# SAMV71_Xplained_Ultra_Shield_Connectors.net
KiCad netlist of a schematic drawn in Altium Designer
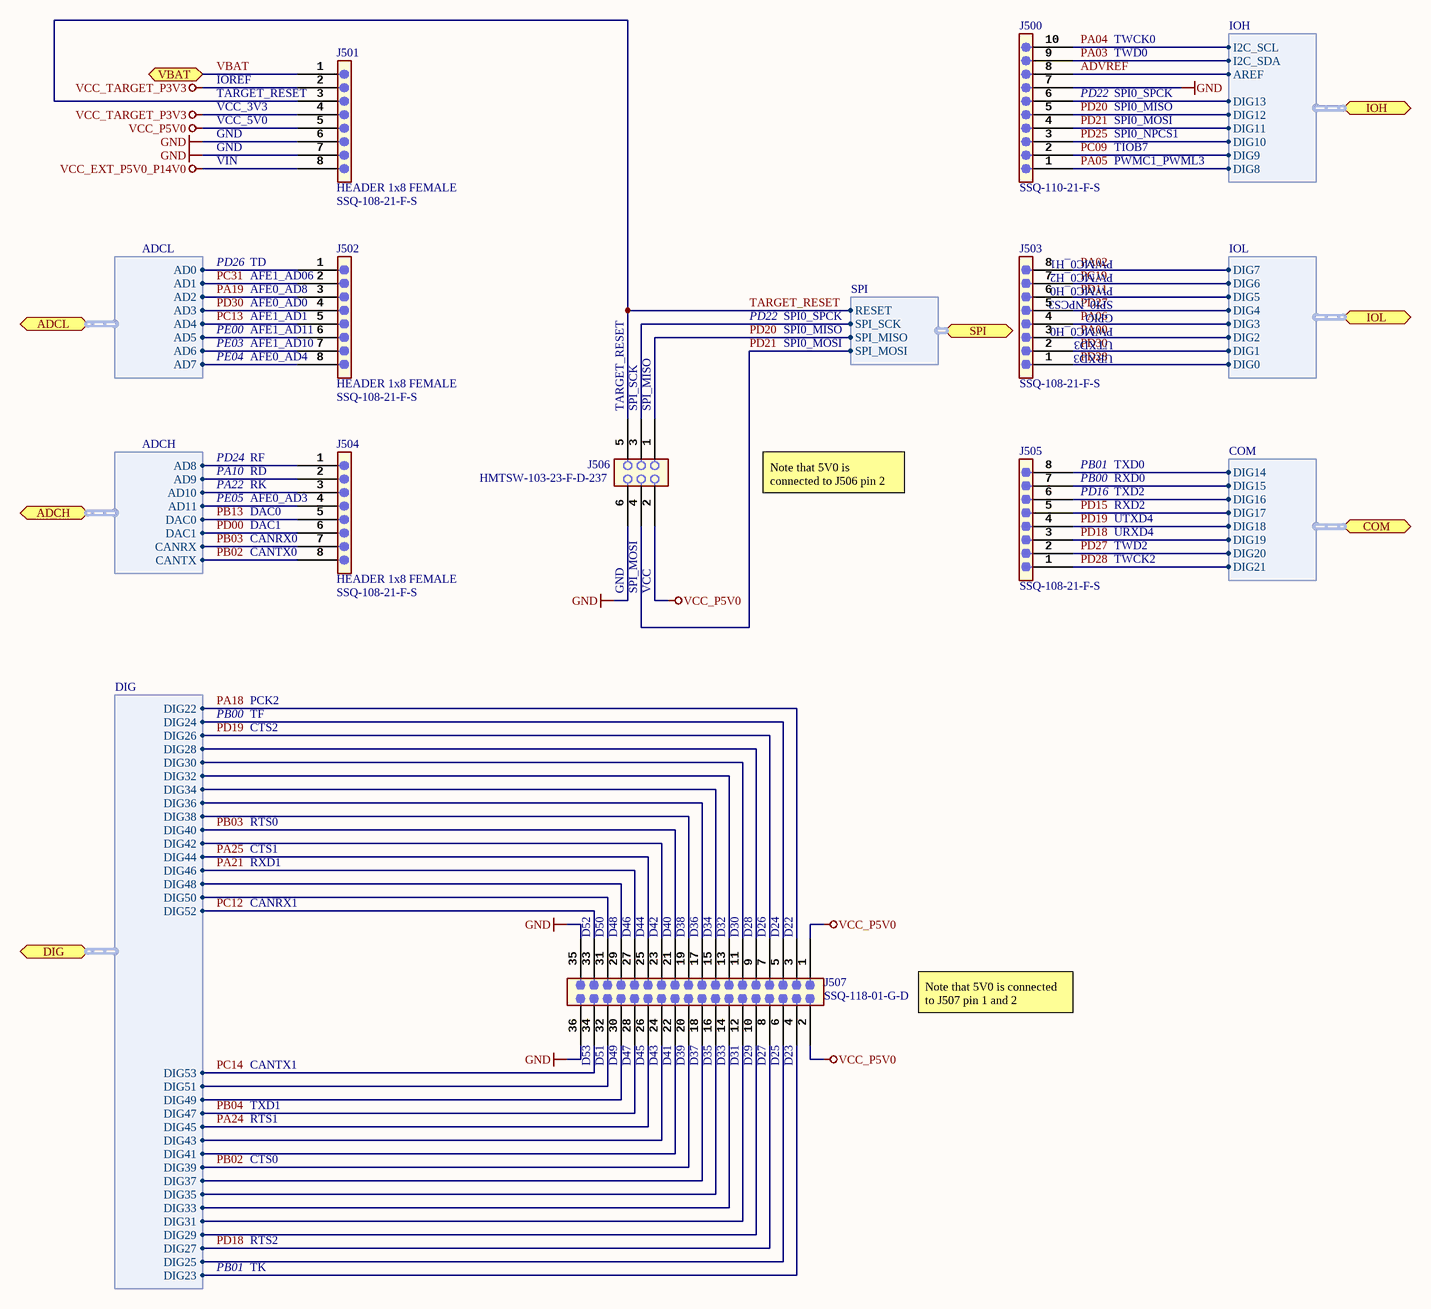
[diagram p0: SAMV71_Xplained_Ultra_Shield_Connectors.SchDoc]

(export (version "E")
  (design (tool "Eeschema 10.0.6"))
  (components
    (comp (ref "J500")
      (value "SSQ-110-21-F-S")
      (footprint "AP8-00822")
      (description "1x10 receptacle pin header, low insertion force, 2.54mm pitch THM, Pin in Paste")
      (fields (field (name "MANUFACTURER") "SAMTEC") (field (name "Comment") "HEADER 1x10 FEMALE"))
      (libsource (lib "AltiumDbLib") (part "HEADER 1x10 FEMALE"))
    )
    (comp (ref "J501")
      (value "HEADER 1x8 FEMALE")
      (footprint "AP8-00823")
      (description "1x8 receptacle pin header, low insertion force, 2.54mm pitch THM, Pin in Paste")
      (fields
        (field (name "ALTIUM_VALUE") "SSQ-108-21-F-S")
        (field (name "MANUFACTURER") "SAMTEC")
        (field (name "MPN") "SSQ-108-21-F-S")
      )
      (libsource (lib "") (part "HEADER 1x8 FEMALE_1"))
    )
    (comp (ref "J502")
      (value "HEADER 1x8 FEMALE")
      (footprint "AP8-00823")
      (description "1x8 receptacle pin header, low insertion force, 2.54mm pitch THM, Pin in Paste")
      (fields
        (field (name "ALTIUM_VALUE") "SSQ-108-21-F-S")
        (field (name "MANUFACTURER") "SAMTEC")
        (field (name "MPN") "SSQ-108-21-F-S")
      )
      (libsource (lib "") (part "HEADER 1x8 FEMALE_1"))
    )
    (comp (ref "J503")
      (value "SSQ-108-21-F-S")
      (footprint "AP8-00823")
      (description "1x8 receptacle pin header, low insertion force, 2.54mm pitch THM, Pin in Paste")
      (fields (field (name "MANUFACTURER") "SAMTEC") (field (name "Comment") "HEADER 1x8 FEMALE"))
      (libsource (lib "AltiumDbLib") (part "HEADER 1x8 FEMALE"))
    )
    (comp (ref "J504")
      (value "HEADER 1x8 FEMALE")
      (footprint "AP8-00823")
      (description "1x8 receptacle pin header, low insertion force, 2.54mm pitch THM, Pin in Paste")
      (fields
        (field (name "ALTIUM_VALUE") "SSQ-108-21-F-S")
        (field (name "MANUFACTURER") "SAMTEC")
        (field (name "MPN") "SSQ-108-21-F-S")
      )
      (libsource (lib "") (part "HEADER 1x8 FEMALE_1"))
    )
    (comp (ref "J505")
      (value "SSQ-108-21-F-S")
      (footprint "AP8-00823")
      (description "1x8 receptacle pin header, low insertion force, 2.54mm pitch THM, Pin in Paste")
      (fields (field (name "MANUFACTURER") "SAMTEC") (field (name "Comment") "HEADER 1x8 FEMALE"))
      (libsource (lib "AltiumDbLib") (part "HEADER 1x8 FEMALE"))
    )
    (comp (ref "J506")
      (value "HMTSW-103-23-F-D-237")
      (footprint "AP8-00182")
      (description "2x3 pin header, 2.54mm pitch, Pin-in-Paste THM")
      (fields (field (name "MANUFACTURER") "SAMTEC") (field (name "Comment") "HEADER 2x3"))
      (libsource (lib "AltiumDbLib") (part "HEADER 2x3"))
    )
    (comp (ref "J507")
      (value "SSQ-118-01-G-D")
      (footprint "AP8-00259")
      (description "2x18 female pin header, 2.54mm pitch, THM")
      (fields (field (name "MANUFACTURER") "SAMTEC") (field (name "Comment") "HEADER 2x18 FEMALE"))
      (libsource (lib "AltiumDbLib") (part "HEADER 2x18 FEMALE"))
    )
  )
  (nets
    (net (code "8") (name "/AD0") (class "Default")
      (node (ref "J502") (pin "1") (pinfunction "1_1") (pintype "passive"))
    )
    (net (code "9") (name "/AD5") (class "Default")
      (node (ref "J502") (pin "6") (pinfunction "6_6") (pintype "passive"))
    )
    (net (code "10") (name "/AD6") (class "Default")
      (node (ref "J502") (pin "7") (pinfunction "7_7") (pintype "passive"))
    )
    (net (code "11") (name "/AD7") (class "Default")
      (node (ref "J502") (pin "8") (pinfunction "8_8") (pintype "passive"))
    )
    (net (code "12") (name "/AD8") (class "Default")
      (node (ref "J504") (pin "1") (pinfunction "1_1") (pintype "passive"))
    )
    (net (code "13") (name "/AD9") (class "Default")
      (node (ref "J504") (pin "2") (pinfunction "2_2") (pintype "passive"))
    )
    (net (code "14") (name "/AD10") (class "Default")
      (node (ref "J504") (pin "3") (pinfunction "3_3") (pintype "passive"))
    )
    (net (code "15") (name "/AD11") (class "Default")
      (node (ref "J504") (pin "4") (pinfunction "4_4") (pintype "passive"))
    )
    (net (code "16") (name "/ADVREF") (class "Default")
      (node (ref "J500") (pin "8") (pinfunction "8_8") (pintype "passive"))
    )
    (net (code "17") (name "/DIG13") (class "Default")
      (node (ref "J500") (pin "6") (pinfunction "6_6") (pintype "passive"))
    )
    (net (code "18") (name "/DIG14") (class "Default")
      (node (ref "J505") (pin "8") (pinfunction "8_8") (pintype "passive"))
    )
    (net (code "19") (name "/DIG15") (class "Default")
      (node (ref "J505") (pin "7") (pinfunction "7_7") (pintype "passive"))
    )
    (net (code "20") (name "/DIG16") (class "Default")
      (node (ref "J505") (pin "6") (pinfunction "6_6") (pintype "passive"))
    )
    (net (code "21") (name "/DIG23") (class "Default")
      (node (ref "J507") (pin "4") (pinfunction "4_4") (pintype "passive"))
    )
    (net (code "22") (name "/DIG24") (class "Default")
      (node (ref "J507") (pin "5") (pinfunction "5_5") (pintype "passive"))
    )
    (net (code "23") (name "/DIG25") (class "Default")
      (node (ref "J507") (pin "6") (pinfunction "6_6") (pintype "passive"))
    )
    (net (code "24") (name "/DIG28") (class "Default")
      (node (ref "J507") (pin "9") (pinfunction "9_9") (pintype "passive"))
    )
    (net (code "25") (name "/DIG29") (class "Default")
      (node (ref "J507") (pin "10") (pinfunction "10_10") (pintype "passive"))
    )
    (net (code "26") (name "/DIG30") (class "Default")
      (node (ref "J507") (pin "11") (pinfunction "11_11") (pintype "passive"))
    )
    (net (code "27") (name "/DIG31") (class "Default")
      (node (ref "J507") (pin "12") (pinfunction "12_12") (pintype "passive"))
    )
    (net (code "28") (name "/DIG32") (class "Default")
      (node (ref "J507") (pin "13") (pinfunction "13_13") (pintype "passive"))
    )
    (net (code "29") (name "/DIG33") (class "Default")
      (node (ref "J507") (pin "14") (pinfunction "14_14") (pintype "passive"))
    )
    (net (code "30") (name "/DIG34") (class "Default")
      (node (ref "J507") (pin "15") (pinfunction "15_15") (pintype "passive"))
    )
    (net (code "31") (name "/DIG35") (class "Default")
      (node (ref "J507") (pin "16") (pinfunction "16_16") (pintype "passive"))
    )
    (net (code "32") (name "/DIG36") (class "Default")
      (node (ref "J507") (pin "17") (pinfunction "17_17") (pintype "passive"))
    )
    (net (code "33") (name "/DIG37") (class "Default")
      (node (ref "J507") (pin "18") (pinfunction "18_18") (pintype "passive"))
    )
    (net (code "34") (name "/DIG38") (class "Default")
      (node (ref "J507") (pin "19") (pinfunction "19_19") (pintype "passive"))
    )
    (net (code "35") (name "/DIG41") (class "Default")
      (node (ref "J507") (pin "22") (pinfunction "22_22") (pintype "passive"))
    )
    (net (code "36") (name "/DIG42") (class "Default")
      (node (ref "J507") (pin "23") (pinfunction "23_23") (pintype "passive"))
    )
    (net (code "37") (name "/DIG43") (class "Default")
      (node (ref "J507") (pin "24") (pinfunction "24_24") (pintype "passive"))
    )
    (net (code "38") (name "/DIG48") (class "Default")
      (node (ref "J507") (pin "29") (pinfunction "29_29") (pintype "passive"))
    )
    (net (code "39") (name "/DIG49") (class "Default")
      (node (ref "J507") (pin "30") (pinfunction "30_30") (pintype "passive"))
    )
    (net (code "40") (name "/DIG50") (class "Default")
      (node (ref "J507") (pin "31") (pinfunction "31_31") (pintype "passive"))
    )
    (net (code "41") (name "/DIG51") (class "Default")
      (node (ref "J507") (pin "32") (pinfunction "32_32") (pintype "passive"))
    )
    (net (code "42") (name "/PA00") (class "Default")
      (node (ref "J503") (pin "3") (pinfunction "3_3") (pintype "passive"))
    )
    (net (code "43") (name "/PA02") (class "Default")
      (node (ref "J503") (pin "8") (pinfunction "8_8") (pintype "passive"))
    )
    (net (code "44") (name "/PA03") (class "Default")
      (node (ref "J500") (pin "9") (pinfunction "9_9") (pintype "passive"))
    )
    (net (code "45") (name "/PA04") (class "Default")
      (node (ref "J500") (pin "10") (pinfunction "10_10") (pintype "passive"))
    )
    (net (code "46") (name "/PA05") (class "Default")
      (node (ref "J500") (pin "1") (pinfunction "1_1") (pintype "passive"))
    )
    (net (code "47") (name "/PA06") (class "Default")
      (node (ref "J503") (pin "4") (pinfunction "4_4") (pintype "passive"))
    )
    (net (code "48") (name "/PA18") (class "Default")
      (node (ref "J507") (pin "3") (pinfunction "3_3") (pintype "passive"))
    )
    (net (code "49") (name "/PA19") (class "Default")
      (node (ref "J502") (pin "3") (pinfunction "3_3") (pintype "passive"))
    )
    (net (code "50") (name "/PA21") (class "Default")
      (node (ref "J507") (pin "27") (pinfunction "27_27") (pintype "passive"))
    )
    (net (code "51") (name "/PA24") (class "Default")
      (node (ref "J507") (pin "26") (pinfunction "26_26") (pintype "passive"))
    )
    (net (code "52") (name "/PA25") (class "Default")
      (node (ref "J507") (pin "25") (pinfunction "25_25") (pintype "passive"))
    )
    (net (code "53") (name "/PB02") (class "Default")
      (node (ref "J504") (pin "8") (pinfunction "8_8") (pintype "passive"))
      (node (ref "J507") (pin "20") (pinfunction "20_20") (pintype "passive"))
    )
    (net (code "54") (name "/PB03") (class "Default")
      (node (ref "J504") (pin "7") (pinfunction "7_7") (pintype "passive"))
      (node (ref "J507") (pin "21") (pinfunction "21_21") (pintype "passive"))
    )
    (net (code "55") (name "/PB04") (class "Default")
      (node (ref "J507") (pin "28") (pinfunction "28_28") (pintype "passive"))
    )
    (net (code "56") (name "/PB13") (class "Default")
      (node (ref "J504") (pin "5") (pinfunction "5_5") (pintype "passive"))
    )
    (net (code "57") (name "/PC09") (class "Default")
      (node (ref "J500") (pin "2") (pinfunction "2_2") (pintype "passive"))
    )
    (net (code "58") (name "/PC12") (class "Default")
      (node (ref "J507") (pin "33") (pinfunction "33_33") (pintype "passive"))
    )
    (net (code "59") (name "/PC13") (class "Default")
      (node (ref "J502") (pin "5") (pinfunction "5_5") (pintype "passive"))
    )
    (net (code "60") (name "/PC14") (class "Default")
      (node (ref "J507") (pin "34") (pinfunction "34_34") (pintype "passive"))
    )
    (net (code "61") (name "/PC19") (class "Default")
      (node (ref "J503") (pin "7") (pinfunction "7_7") (pintype "passive"))
    )
    (net (code "62") (name "/PC31") (class "Default")
      (node (ref "J502") (pin "2") (pinfunction "2_2") (pintype "passive"))
    )
    (net (code "63") (name "/PD00") (class "Default")
      (node (ref "J504") (pin "6") (pinfunction "6_6") (pintype "passive"))
    )
    (net (code "64") (name "/PD11") (class "Default")
      (node (ref "J503") (pin "6") (pinfunction "6_6") (pintype "passive"))
    )
    (net (code "65") (name "/PD15") (class "Default")
      (node (ref "J505") (pin "5") (pinfunction "5_5") (pintype "passive"))
    )
    (net (code "66") (name "/PD18") (class "Default")
      (node (ref "J505") (pin "3") (pinfunction "3_3") (pintype "passive"))
      (node (ref "J507") (pin "8") (pinfunction "8_8") (pintype "passive"))
    )
    (net (code "67") (name "/PD19") (class "Default")
      (node (ref "J505") (pin "4") (pinfunction "4_4") (pintype "passive"))
      (node (ref "J507") (pin "7") (pinfunction "7_7") (pintype "passive"))
    )
    (net (code "68") (name "/PD20") (class "Default")
      (node (ref "J500") (pin "5") (pinfunction "5_5") (pintype "passive"))
      (node (ref "J506") (pin "1") (pinfunction "1_1") (pintype "passive"))
    )
    (net (code "69") (name "/PD21") (class "Default")
      (node (ref "J500") (pin "4") (pinfunction "4_4") (pintype "passive"))
      (node (ref "J506") (pin "4") (pinfunction "4_4") (pintype "passive"))
    )
    (net (code "70") (name "/PD25") (class "Default")
      (node (ref "J500") (pin "3") (pinfunction "3_3") (pintype "passive"))
    )
    (net (code "71") (name "/PD27") (class "Default")
      (node (ref "J503") (pin "5") (pinfunction "5_5") (pintype "passive"))
      (node (ref "J505") (pin "2") (pinfunction "2_2") (pintype "passive"))
    )
    (net (code "72") (name "/PD28") (class "Default")
      (node (ref "J503") (pin "1") (pinfunction "1_1") (pintype "passive"))
      (node (ref "J505") (pin "1") (pinfunction "1_1") (pintype "passive"))
    )
    (net (code "73") (name "/PD30") (class "Default")
      (node (ref "J502") (pin "4") (pinfunction "4_4") (pintype "passive"))
      (node (ref "J503") (pin "2") (pinfunction "2_2") (pintype "passive"))
    )
    (net (code "74") (name "/SPI_SCK") (class "Default")
      (node (ref "J506") (pin "3") (pinfunction "3_3") (pintype "passive"))
    )
    (net (code "75") (name "/TARGET_RESET") (class "Default")
      (node (ref "J501") (pin "3") (pinfunction "3_3") (pintype "passive"))
      (node (ref "J506") (pin "5") (pinfunction "5_5") (pintype "passive"))
    )
    (net (code "76") (name "/VBAT") (class "Default")
      (node (ref "J501") (pin "1") (pinfunction "1_1") (pintype "passive"))
    )
    (net (code "84") (name "GND") (class "Default")
      (node (ref "J500") (pin "7") (pinfunction "7_7") (pintype "passive"))
      (node (ref "J501") (pin "6") (pinfunction "6_6") (pintype "passive"))
      (node (ref "J501") (pin "7") (pinfunction "7_7") (pintype "passive"))
      (node (ref "J506") (pin "6") (pinfunction "6_6") (pintype "passive"))
      (node (ref "J507") (pin "35") (pinfunction "35_35") (pintype "passive"))
      (node (ref "J507") (pin "36") (pinfunction "36_36") (pintype "passive"))
    )
    (net (code "85") (name "VCC_EXT_P5V0_P14V0") (class "Default")
      (node (ref "J501") (pin "8") (pinfunction "8_8") (pintype "passive"))
    )
    (net (code "86") (name "VCC_P5V0") (class "Default")
      (node (ref "J501") (pin "5") (pinfunction "5_5") (pintype "passive"))
      (node (ref "J506") (pin "2") (pinfunction "2_2") (pintype "passive"))
      (node (ref "J507") (pin "1") (pinfunction "1_1") (pintype "passive"))
      (node (ref "J507") (pin "2") (pinfunction "2_2") (pintype "passive"))
    )
    (net (code "87") (name "VCC_TARGET_P3V3") (class "Default")
      (node (ref "J501") (pin "2") (pinfunction "2_2") (pintype "passive"))
      (node (ref "J501") (pin "4") (pinfunction "4_4") (pintype "passive"))
    )
  )
)
